# ClassDAmp.net
KiCad netlist of a schematic drawn in EAGLE
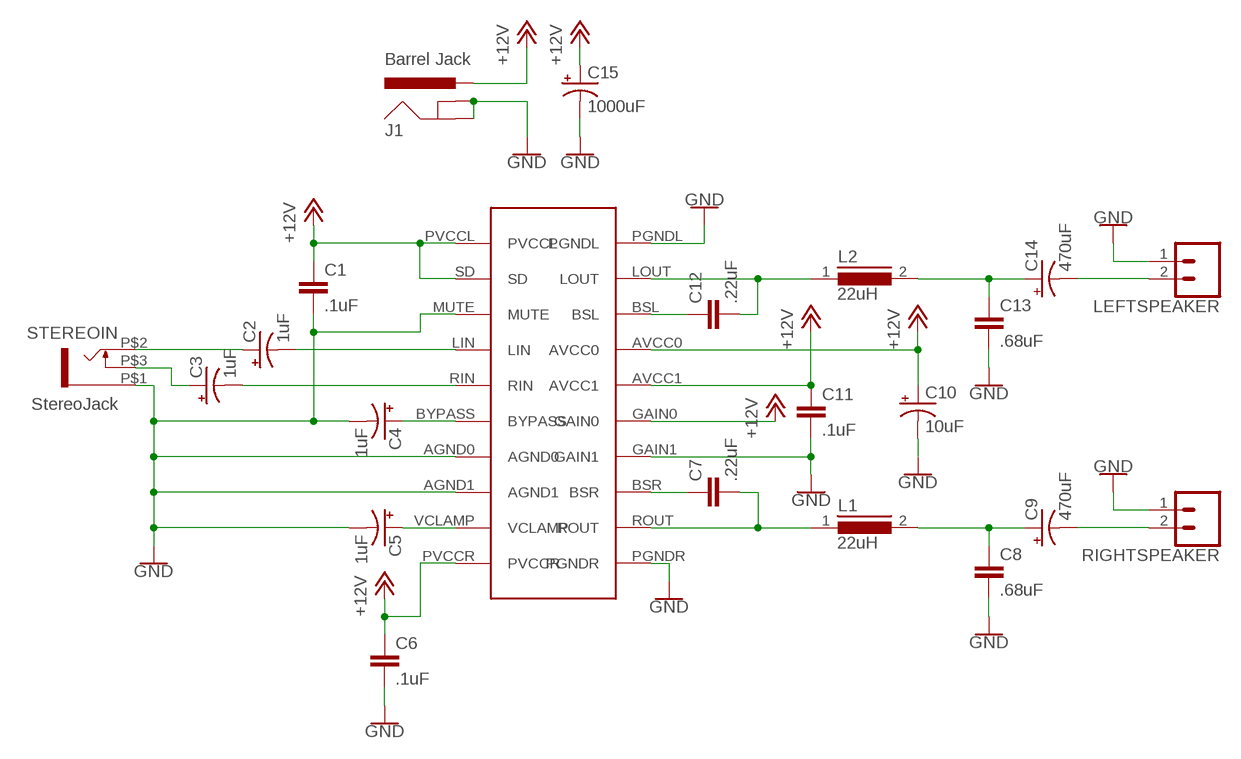
[diagram p0: schematic, sheet 1]

(export (version "E")
  (design (tool "Eeschema 10.0.6"))
  (components
    (comp (ref "C1")
      (value ".1uF")
      (footprint "eagle-import:0805")
      (libsource (lib "eagle-import") (part "0.33UF/330NF-0805-50V-10%"))
    )
    (comp (ref "C2")
      (value "1uF")
      (footprint "eagle-import:CPOL-RADIAL-2.5MM-6.5MM")
      (libsource (lib "eagle-import") (part "100UF-POLAR-RADIAL-2.5MM-25V-20%"))
    )
    (comp (ref "C3")
      (value "1uF")
      (footprint "eagle-import:CPOL-RADIAL-2.5MM-6.5MM")
      (libsource (lib "eagle-import") (part "100UF-POLAR-RADIAL-2.5MM-25V-20%"))
    )
    (comp (ref "C4")
      (value "1uF")
      (footprint "eagle-import:CPOL-RADIAL-2.5MM-6.5MM")
      (libsource (lib "eagle-import") (part "100UF-POLAR-RADIAL-2.5MM-25V-20%"))
    )
    (comp (ref "C5")
      (value "1uF")
      (footprint "eagle-import:CPOL-RADIAL-2.5MM-6.5MM")
      (libsource (lib "eagle-import") (part "100UF-POLAR-RADIAL-2.5MM-25V-20%"))
    )
    (comp (ref "C6")
      (value ".1uF")
      (footprint "eagle-import:0805")
      (libsource (lib "eagle-import") (part "0.33UF/330NF-0805-50V-10%"))
    )
    (comp (ref "C7")
      (value ".22uF")
      (footprint "eagle-import:0805")
      (libsource (lib "eagle-import") (part "0.33UF/330NF-0805-50V-10%"))
    )
    (comp (ref "C8")
      (value ".68uF")
      (footprint "eagle-import:0805")
      (libsource (lib "eagle-import") (part "0.33UF/330NF-0805-50V-10%"))
    )
    (comp (ref "C9")
      (value "470uF")
      (footprint "eagle-import:CPOL-RADIAL-2.5MM-6.5MM")
      (libsource (lib "eagle-import") (part "100UF-POLAR-RADIAL-2.5MM-25V-20%"))
    )
    (comp (ref "C10")
      (value "10uF")
      (footprint "eagle-import:CPOL-RADIAL-2.5MM-6.5MM")
      (libsource (lib "eagle-import") (part "100UF-POLAR-RADIAL-2.5MM-25V-20%"))
    )
    (comp (ref "C11")
      (value ".1uF")
      (footprint "eagle-import:0805")
      (libsource (lib "eagle-import") (part "0.33UF/330NF-0805-50V-10%"))
    )
    (comp (ref "C12")
      (value ".22uF")
      (footprint "eagle-import:0805")
      (libsource (lib "eagle-import") (part "0.33UF/330NF-0805-50V-10%"))
    )
    (comp (ref "C13")
      (value ".68uF")
      (footprint "eagle-import:0805")
      (libsource (lib "eagle-import") (part "0.33UF/330NF-0805-50V-10%"))
    )
    (comp (ref "C14")
      (value "470uF")
      (footprint "eagle-import:CPOL-RADIAL-2.5MM-6.5MM")
      (libsource (lib "eagle-import") (part "100UF-POLAR-RADIAL-2.5MM-25V-20%"))
    )
    (comp (ref "C15")
      (value "1000uF")
      (footprint "eagle-import:CPOL-RADIAL-2.5MM-6.5MM")
      (libsource (lib "eagle-import") (part "100UF-POLAR-RADIAL-2.5MM-25V-20%"))
    )
    (comp (ref "J1")
      (value "Barrel Jack")
      (footprint "eagle-import:POWER_JACK_PTH_BREAD")
      (libsource (lib "eagle-import") (part "POWER_JACKPTH_BREAD"))
    )
    (comp (ref "L1")
      (value "22uH")
      (footprint "eagle-import:82114R")
      (libsource (lib "eagle-import") (part "82114R"))
    )
    (comp (ref "L2")
      (value "22uH")
      (footprint "eagle-import:82114R")
      (libsource (lib "eagle-import") (part "82114R"))
    )
    (comp (ref "LEFTSPEAKER")
      (value "CONN_023.5MM")
      (footprint "eagle-import:SCREWTERMINAL-3.5MM-2")
      (libsource (lib "eagle-import") (part "CONN_023.5MM"))
    )
    (comp (ref "RIGHTSPEAKER")
      (value "CONN_023.5MM")
      (footprint "eagle-import:SCREWTERMINAL-3.5MM-2")
      (libsource (lib "eagle-import") (part "CONN_023.5MM"))
    )
    (comp (ref "STEREOIN")
      (value "StereoJack")
      (footprint "eagle-import:HORIZONTAL_STEREO_JACK")
      (libsource (lib "eagle-import") (part "HORIZONTAL_STERO_JACK"))
    )
    (comp (ref "U$1")
      (value "TPA3122")
      (footprint "eagle-import:TPA3122")
      (libsource (lib "eagle-import") (part "TPA3122"))
    )
  )
  (nets
    (net (code "1") (name "+12V") (class "Default")
      (node (ref "C1") (pin "1") (pinfunction "1_1") (pintype "passive"))
      (node (ref "C10") (pin "1") (pinfunction "+_1") (pintype "passive"))
      (node (ref "C11") (pin "1") (pinfunction "1_1") (pintype "passive"))
      (node (ref "C15") (pin "1") (pinfunction "+_1") (pintype "passive"))
      (node (ref "C6") (pin "1") (pinfunction "1_1") (pintype "passive"))
      (node (ref "J1") (pin "PWR") (pinfunction "PWR_PWR") (pintype "bidirectional"))
      (node (ref "U$1") (pin "AVCC0") (pinfunction "AVCC0_AVCC0") (pintype "bidirectional"))
      (node (ref "U$1") (pin "AVCC1") (pinfunction "AVCC1_AVCC1") (pintype "bidirectional"))
      (node (ref "U$1") (pin "GAIN0") (pinfunction "GAIN0_GAIN0") (pintype "bidirectional"))
      (node (ref "U$1") (pin "PVCCL") (pinfunction "PVCCL_PVCCL") (pintype "bidirectional"))
      (node (ref "U$1") (pin "PVCCR") (pinfunction "PVCCR_PVCCR") (pintype "bidirectional"))
      (node (ref "U$1") (pin "SD") (pinfunction "SD_SD") (pintype "bidirectional"))
    )
    (net (code "2") (name "GND") (class "Default")
      (node (ref "C1") (pin "2") (pinfunction "2_2") (pintype "passive"))
      (node (ref "C10") (pin "2") (pinfunction "-_2") (pintype "passive"))
      (node (ref "C11") (pin "2") (pinfunction "2_2") (pintype "passive"))
      (node (ref "C13") (pin "2") (pinfunction "2_2") (pintype "passive"))
      (node (ref "C15") (pin "2") (pinfunction "-_2") (pintype "passive"))
      (node (ref "C4") (pin "2") (pinfunction "-_2") (pintype "passive"))
      (node (ref "C5") (pin "2") (pinfunction "-_2") (pintype "passive"))
      (node (ref "C6") (pin "2") (pinfunction "2_2") (pintype "passive"))
      (node (ref "C8") (pin "2") (pinfunction "2_2") (pintype "passive"))
      (node (ref "J1") (pin "GND") (pinfunction "GND_GND") (pintype "bidirectional"))
      (node (ref "J1") (pin "GNDBREAK") (pinfunction "GNDBREAK_GNDBREAK") (pintype "bidirectional"))
      (node (ref "LEFTSPEAKER") (pin "1") (pinfunction "1_1") (pintype "passive"))
      (node (ref "RIGHTSPEAKER") (pin "1") (pinfunction "1_1") (pintype "passive"))
      (node (ref "STEREOIN") (pin "P$1") (pinfunction "1_P$1") (pintype "passive"))
      (node (ref "U$1") (pin "AGND0") (pinfunction "AGND0_AGND0") (pintype "bidirectional"))
      (node (ref "U$1") (pin "AGND1") (pinfunction "AGND1_AGND1") (pintype "bidirectional"))
      (node (ref "U$1") (pin "GAIN1") (pinfunction "GAIN1_GAIN1") (pintype "bidirectional"))
      (node (ref "U$1") (pin "MUTE") (pinfunction "MUTE_MUTE") (pintype "bidirectional"))
      (node (ref "U$1") (pin "PGNDL") (pinfunction "PGNDL_PGNDL") (pintype "bidirectional"))
      (node (ref "U$1") (pin "PGNDR") (pinfunction "PGNDR_PGNDR") (pintype "bidirectional"))
    )
    (net (code "3") (name "Net-(C2-+)") (class "Default")
      (node (ref "C2") (pin "1") (pinfunction "+_1") (pintype "passive"))
      (node (ref "STEREOIN") (pin "P$2") (pinfunction "2_P$2") (pintype "passive"))
    )
    (net (code "4") (name "Net-(C2--)") (class "Default")
      (node (ref "C2") (pin "2") (pinfunction "-_2") (pintype "passive"))
      (node (ref "U$1") (pin "LIN") (pinfunction "LIN_LIN") (pintype "bidirectional"))
    )
    (net (code "5") (name "Net-(C3-+)") (class "Default")
      (node (ref "C3") (pin "1") (pinfunction "+_1") (pintype "passive"))
      (node (ref "STEREOIN") (pin "P$3") (pinfunction "3_P$3") (pintype "passive"))
    )
    (net (code "6") (name "Net-(C3--)") (class "Default")
      (node (ref "C3") (pin "2") (pinfunction "-_2") (pintype "passive"))
      (node (ref "U$1") (pin "RIN") (pinfunction "RIN_RIN") (pintype "bidirectional"))
    )
    (net (code "7") (name "Net-(C4-+)") (class "Default")
      (node (ref "C4") (pin "1") (pinfunction "+_1") (pintype "passive"))
      (node (ref "U$1") (pin "BYPASS") (pinfunction "BYPASS_BYPASS") (pintype "bidirectional"))
    )
    (net (code "8") (name "Net-(C5-+)") (class "Default")
      (node (ref "C5") (pin "1") (pinfunction "+_1") (pintype "passive"))
      (node (ref "U$1") (pin "VCLAMP") (pinfunction "VCLAMP_VCLAMP") (pintype "bidirectional"))
    )
    (net (code "9") (name "Net-(C7-Pad1)") (class "Default")
      (node (ref "C7") (pin "1") (pinfunction "1_1") (pintype "passive"))
      (node (ref "U$1") (pin "BSR") (pinfunction "BSR_BSR") (pintype "bidirectional"))
    )
    (net (code "10") (name "Net-(C7-Pad2)") (class "Default")
      (node (ref "C7") (pin "2") (pinfunction "2_2") (pintype "passive"))
      (node (ref "L1") (pin "1") (pinfunction "1_1") (pintype "passive"))
      (node (ref "U$1") (pin "ROUT") (pinfunction "ROUT_ROUT") (pintype "bidirectional"))
    )
    (net (code "11") (name "Net-(C9-+)") (class "Default")
      (node (ref "C8") (pin "1") (pinfunction "1_1") (pintype "passive"))
      (node (ref "C9") (pin "1") (pinfunction "+_1") (pintype "passive"))
      (node (ref "L1") (pin "2") (pinfunction "2_2") (pintype "passive"))
    )
    (net (code "12") (name "Net-(C9--)") (class "Default")
      (node (ref "C9") (pin "2") (pinfunction "-_2") (pintype "passive"))
      (node (ref "RIGHTSPEAKER") (pin "2") (pinfunction "2_2") (pintype "passive"))
    )
    (net (code "13") (name "Net-(C12-Pad1)") (class "Default")
      (node (ref "C12") (pin "1") (pinfunction "1_1") (pintype "passive"))
      (node (ref "U$1") (pin "BSL") (pinfunction "BSL_BSL") (pintype "bidirectional"))
    )
    (net (code "14") (name "Net-(C12-Pad2)") (class "Default")
      (node (ref "C12") (pin "2") (pinfunction "2_2") (pintype "passive"))
      (node (ref "L2") (pin "1") (pinfunction "1_1") (pintype "passive"))
      (node (ref "U$1") (pin "LOUT") (pinfunction "LOUT_LOUT") (pintype "bidirectional"))
    )
    (net (code "15") (name "Net-(C14-+)") (class "Default")
      (node (ref "C13") (pin "1") (pinfunction "1_1") (pintype "passive"))
      (node (ref "C14") (pin "1") (pinfunction "+_1") (pintype "passive"))
      (node (ref "L2") (pin "2") (pinfunction "2_2") (pintype "passive"))
    )
    (net (code "16") (name "Net-(C14--)") (class "Default")
      (node (ref "C14") (pin "2") (pinfunction "-_2") (pintype "passive"))
      (node (ref "LEFTSPEAKER") (pin "2") (pinfunction "2_2") (pintype "passive"))
    )
  )
)
